# Power.net
KiCad netlist of a schematic drawn in Altium Designer
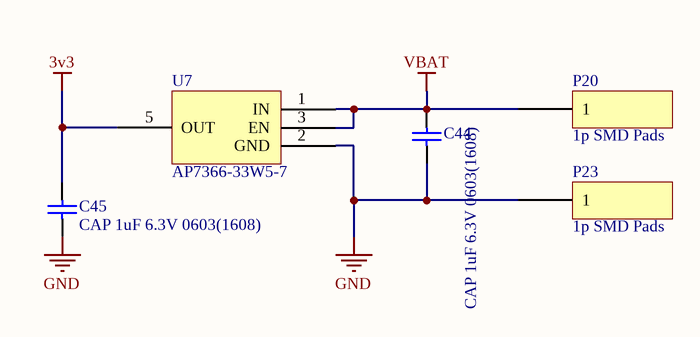
[diagram p0: Power.SchDoc]

(export (version "E")
  (design (tool "Eeschema 10.0.6"))
  (components
    (comp (ref "C44")
      (value "CAP 1uF 6.3V 0603(1608)")
      (footprint "CAPC0603(1608)100_L")
      (description "CAP 1uF 6.3V ±20% 0603 (1608 Metric) Thickness 1mm SMD")
      (fields (field (name "TOLERANCE") "Â±20%"))
      (libsource (lib "Altium Content Vault") (part "CAP"))
    )
    (comp (ref "C45")
      (value "CAP 1uF 6.3V 0603(1608)")
      (footprint "CAPC0603(1608)100_L")
      (description "CAP 1uF 6.3V ±20% 0603 (1608 Metric) Thickness 1mm SMD")
      (fields (field (name "TOLERANCE") "Â±20%"))
      (libsource (lib "Altium Content Vault") (part "CAP"))
    )
    (comp (ref "P20")
      (value "1p SMD Pads")
      (footprint "1p SMD pad")
      (libsource (lib "parts (carol's conflicted copy 2019-04-30)") (part "1p SMD"))
    )
    (comp (ref "P23")
      (value "1p SMD Pads")
      (footprint "1p SMD pad")
      (libsource (lib "parts (carol's conflicted copy 2019-04-30)") (part "1p SMD"))
    )
    (comp (ref "U7")
      (value "AP7366-33W5-7")
      (footprint "SOT95P280X145-5N")
      (description "Linear Voltage Regulator IC 1 Output 600mA SOT-25")
      (libsource (lib "parts") (part "AP7366-33W5-7"))
    )
  )
  (nets
    (net (code "1") (name "3v3") (class "Default")
      (node (ref "C45") (pin "2") (pinfunction "2_2") (pintype "passive"))
      (node (ref "U7") (pin "5") (pinfunction "OUT_5") (pintype "passive"))
    )
    (net (code "2") (name "GND") (class "Default")
      (node (ref "C44") (pin "1") (pinfunction "1_1") (pintype "passive"))
      (node (ref "C45") (pin "1") (pinfunction "1_1") (pintype "passive"))
      (node (ref "P23") (pin "1") (pinfunction "1_1") (pintype "passive"))
      (node (ref "U7") (pin "2") (pinfunction "GND_2") (pintype "passive"))
    )
    (net (code "3") (name "VBAT") (class "Default")
      (node (ref "C44") (pin "2") (pinfunction "2_2") (pintype "passive"))
      (node (ref "P20") (pin "1") (pinfunction "1_1") (pintype "passive"))
      (node (ref "U7") (pin "1") (pinfunction "IN_1") (pintype "passive"))
      (node (ref "U7") (pin "3") (pinfunction "EN_3") (pintype "passive"))
    )
  )
)
